# MCU.net
KiCad netlist of a schematic drawn in Altium Designer
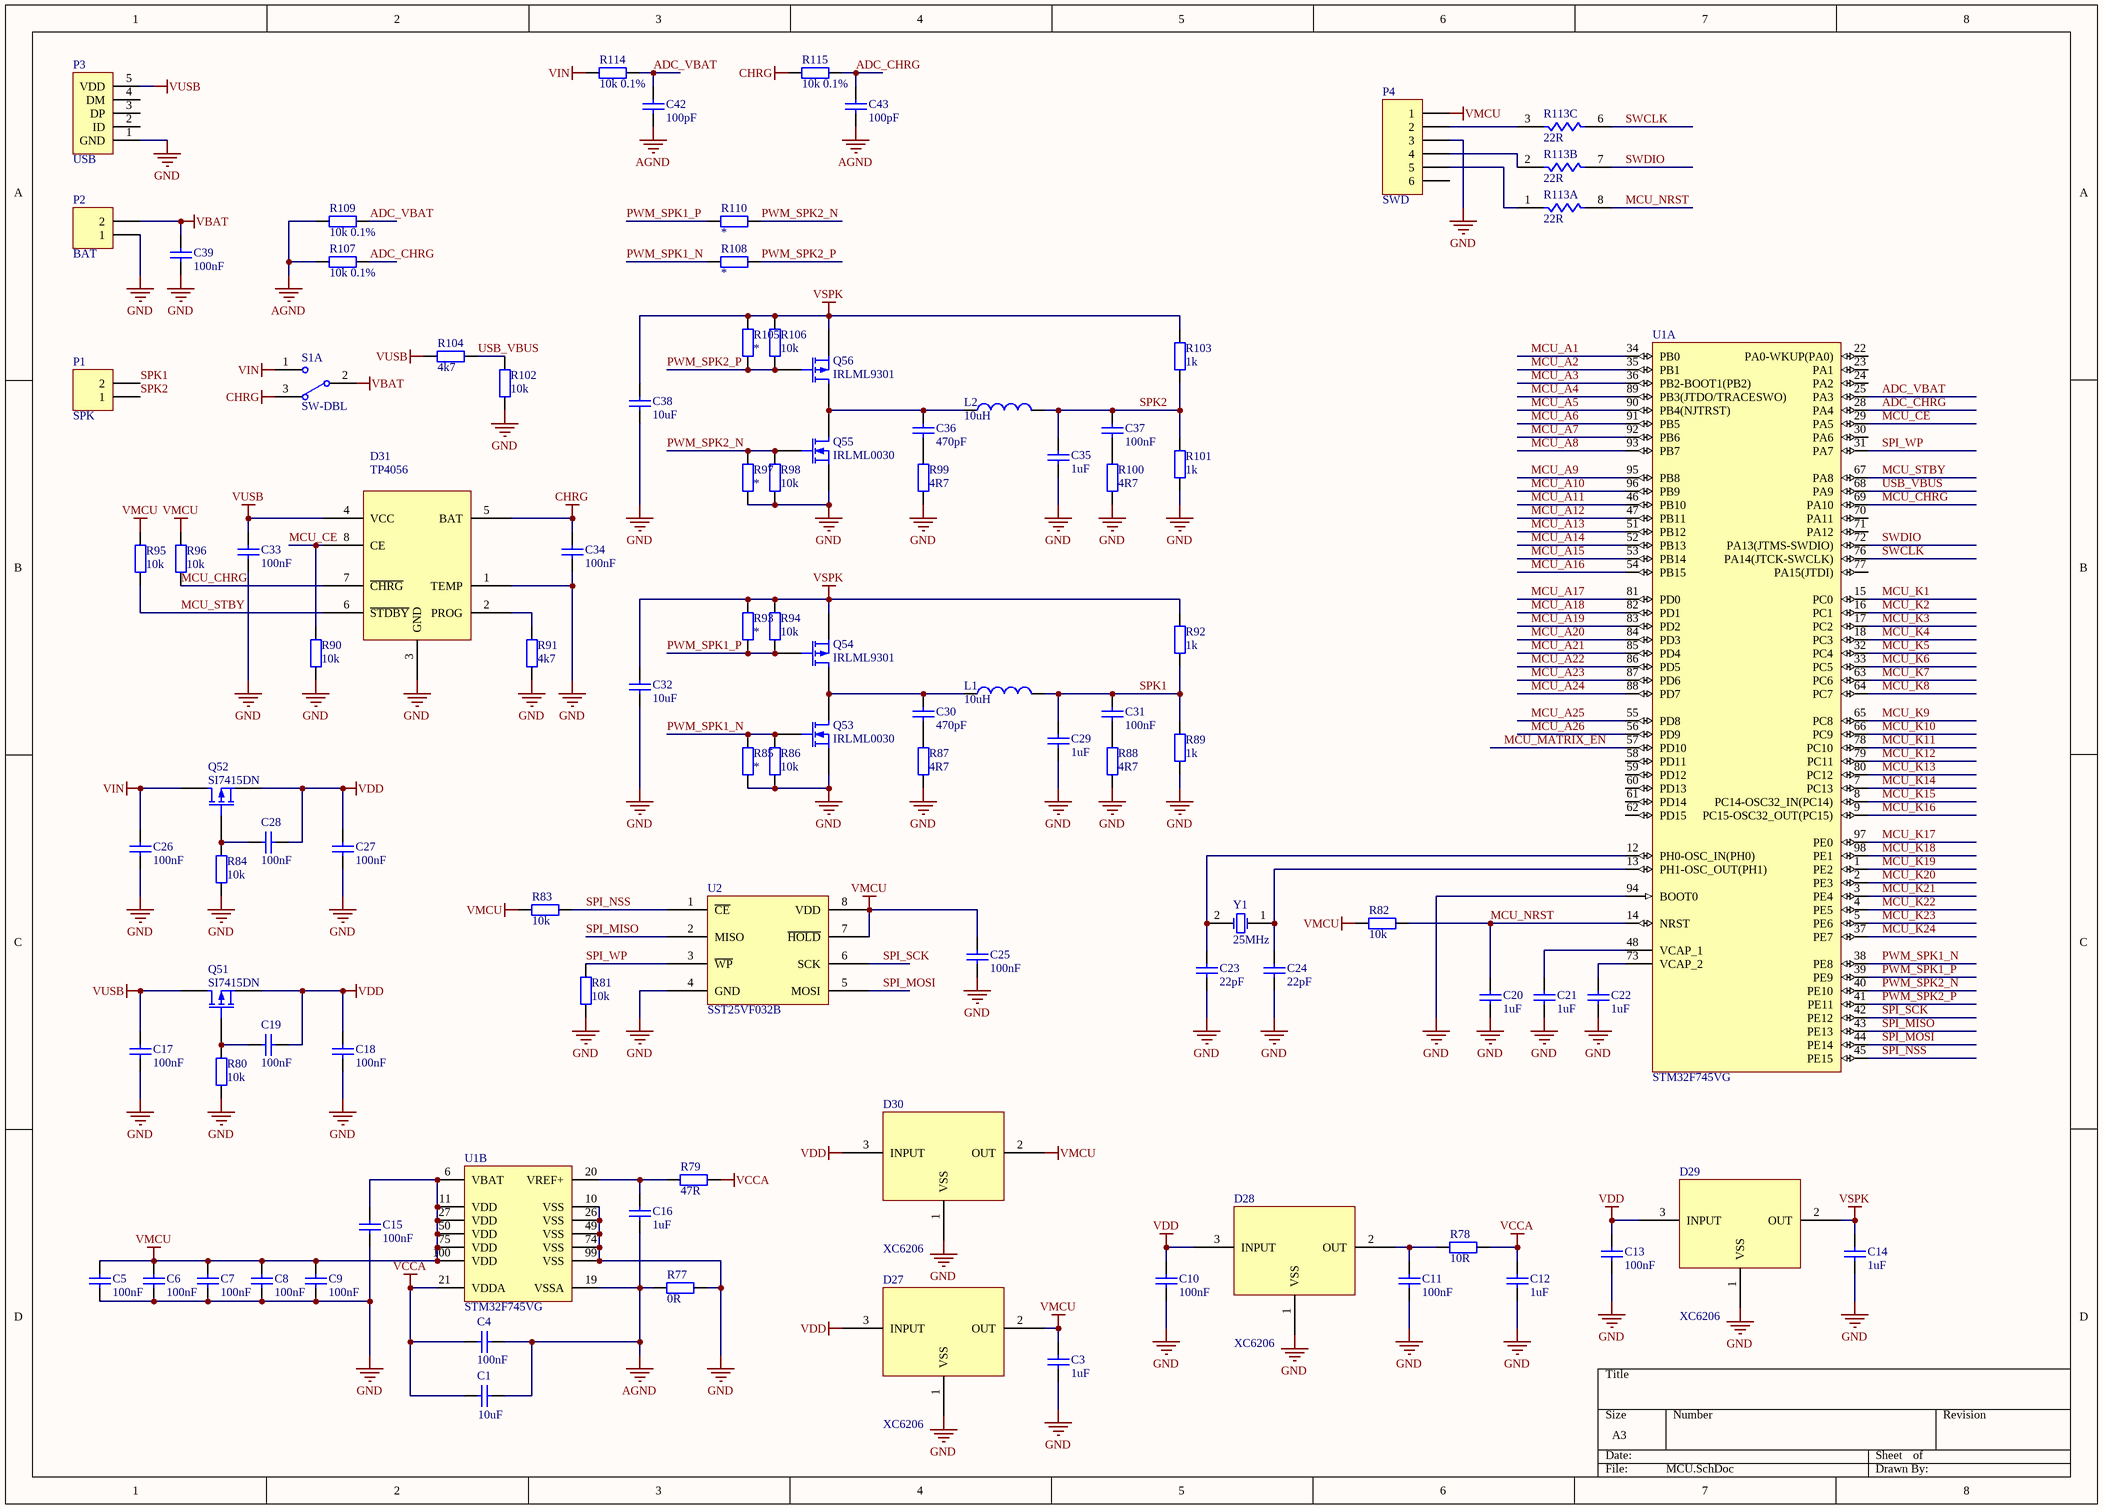
[diagram p0: MCU.SchDoc]

(export (version "E")
  (design (tool "Eeschema 10.0.6"))
  (components
    (comp (ref "C1")
      (value "10uF")
      (footprint "c1206")
      (description "Capacitor")
      (fields (field (name "Comment") "Cap") (field (name "PUBLISHER") "Altium Limited"))
      (libsource (lib "Miscellaneous Devices") (part "Cap"))
    )
    (comp (ref "C3")
      (value "1uF")
      (footprint "C0603")
      (description "Capacitor")
      (fields (field (name "Comment") "Cap") (field (name "PUBLISHER") "Altium Limited"))
      (libsource (lib "Lib_Sch") (part "Cap"))
    )
    (comp (ref "C4")
      (value "100nF")
      (footprint "C0603")
      (description "Capacitor")
      (fields (field (name "Comment") "Cap") (field (name "PUBLISHER") "Altium Limited"))
      (libsource (lib "Lib_Sch") (part "Cap"))
    )
    (comp (ref "C5")
      (value "100nF")
      (footprint "C0603")
      (description "Capacitor")
      (fields (field (name "Comment") "Cap") (field (name "PUBLISHER") "Altium Limited"))
      (libsource (lib "Lib_Sch") (part "Cap"))
    )
    (comp (ref "C6")
      (value "100nF")
      (footprint "C0603")
      (description "Capacitor")
      (fields (field (name "Comment") "Cap") (field (name "PUBLISHER") "Altium Limited"))
      (libsource (lib "Lib_Sch") (part "Cap"))
    )
    (comp (ref "C7")
      (value "100nF")
      (footprint "C0603")
      (description "Capacitor")
      (fields (field (name "Comment") "Cap") (field (name "PUBLISHER") "Altium Limited"))
      (libsource (lib "Lib_Sch") (part "Cap"))
    )
    (comp (ref "C8")
      (value "100nF")
      (footprint "C0603")
      (description "Capacitor")
      (fields (field (name "Comment") "Cap") (field (name "PUBLISHER") "Altium Limited"))
      (libsource (lib "Lib_Sch") (part "Cap"))
    )
    (comp (ref "C9")
      (value "100nF")
      (footprint "C0603")
      (description "Capacitor")
      (fields (field (name "Comment") "Cap") (field (name "PUBLISHER") "Altium Limited"))
      (libsource (lib "Lib_Sch") (part "Cap"))
    )
    (comp (ref "C10")
      (value "100nF")
      (footprint "C0603")
      (description "Capacitor")
      (fields (field (name "Comment") "Cap") (field (name "PUBLISHER") "Altium Limited"))
      (libsource (lib "Lib_Sch") (part "Cap"))
    )
    (comp (ref "C11")
      (value "100nF")
      (footprint "C0603")
      (description "Capacitor")
      (fields (field (name "Comment") "Cap") (field (name "PUBLISHER") "Altium Limited"))
      (libsource (lib "Lib_Sch") (part "Cap"))
    )
    (comp (ref "C12")
      (value "1uF")
      (footprint "C0603")
      (description "Capacitor")
      (fields (field (name "Comment") "Cap") (field (name "PUBLISHER") "Altium Limited"))
      (libsource (lib "Lib_Sch") (part "Cap"))
    )
    (comp (ref "C13")
      (value "100nF")
      (footprint "C0603")
      (description "Capacitor")
      (fields (field (name "Comment") "Cap") (field (name "PUBLISHER") "Altium Limited"))
      (libsource (lib "Lib_Sch") (part "Cap"))
    )
    (comp (ref "C14")
      (value "1uF")
      (footprint "C0603")
      (description "Capacitor")
      (fields (field (name "Comment") "Cap") (field (name "PUBLISHER") "Altium Limited"))
      (libsource (lib "Lib_Sch") (part "Cap"))
    )
    (comp (ref "C15")
      (value "100nF")
      (footprint "C0603")
      (description "Capacitor")
      (fields (field (name "Comment") "Cap") (field (name "PUBLISHER") "Altium Limited"))
      (libsource (lib "Lib_Sch") (part "Cap"))
    )
    (comp (ref "C16")
      (value "1uF")
      (footprint "C0603")
      (description "Capacitor")
      (fields (field (name "Comment") "Cap") (field (name "PUBLISHER") "Altium Limited"))
      (libsource (lib "Lib_Sch") (part "Cap"))
    )
    (comp (ref "C17")
      (value "100nF")
      (footprint "C0603")
      (description "Capacitor")
      (fields (field (name "Comment") "Cap") (field (name "PUBLISHER") "Altium Limited"))
      (libsource (lib "Lib_Sch") (part "Cap"))
    )
    (comp (ref "C18")
      (value "100nF")
      (footprint "C0603")
      (description "Capacitor")
      (fields (field (name "Comment") "Cap") (field (name "PUBLISHER") "Altium Limited"))
      (libsource (lib "Lib_Sch") (part "Cap"))
    )
    (comp (ref "C19")
      (value "100nF")
      (footprint "C0603")
      (description "Capacitor")
      (fields (field (name "Comment") "Cap") (field (name "PUBLISHER") "Altium Limited"))
      (libsource (lib "Lib_Sch") (part "Cap"))
    )
    (comp (ref "C20")
      (value "1uF")
      (footprint "C0603")
      (description "Capacitor")
      (fields (field (name "Comment") "Cap") (field (name "PUBLISHER") "Altium Limited"))
      (libsource (lib "Lib_Sch") (part "Cap"))
    )
    (comp (ref "C21")
      (value "1uF")
      (footprint "C0603")
      (description "Capacitor")
      (fields (field (name "Comment") "Cap") (field (name "PUBLISHER") "Altium Limited"))
      (libsource (lib "Lib_Sch") (part "Cap"))
    )
    (comp (ref "C22")
      (value "1uF")
      (footprint "C0603")
      (description "Capacitor")
      (fields (field (name "Comment") "Cap") (field (name "PUBLISHER") "Altium Limited"))
      (libsource (lib "Lib_Sch") (part "Cap"))
    )
    (comp (ref "C23")
      (value "22pF")
      (footprint "c0603")
      (description "Capacitor")
      (fields (field (name "PUBLISHER") "Altium Limited"))
      (libsource (lib "") (part "Cap_1"))
    )
    (comp (ref "C24")
      (value "22pF")
      (footprint "c0603")
      (description "Capacitor")
      (fields (field (name "PUBLISHER") "Altium Limited"))
      (libsource (lib "") (part "Cap_1"))
    )
    (comp (ref "C25")
      (value "100nF")
      (footprint "C0603")
      (description "Capacitor")
      (fields (field (name "Comment") "Cap") (field (name "PUBLISHER") "Altium Limited"))
      (libsource (lib "Lib_Sch") (part "Cap"))
    )
    (comp (ref "C26")
      (value "100nF")
      (footprint "C0603")
      (description "Capacitor")
      (fields (field (name "Comment") "Cap") (field (name "PUBLISHER") "Altium Limited"))
      (libsource (lib "Lib_Sch") (part "Cap"))
    )
    (comp (ref "C27")
      (value "100nF")
      (footprint "C0603")
      (description "Capacitor")
      (fields (field (name "Comment") "Cap") (field (name "PUBLISHER") "Altium Limited"))
      (libsource (lib "Lib_Sch") (part "Cap"))
    )
    (comp (ref "C28")
      (value "100nF")
      (footprint "C0603")
      (description "Capacitor")
      (fields (field (name "Comment") "Cap") (field (name "PUBLISHER") "Altium Limited"))
      (libsource (lib "Lib_Sch") (part "Cap"))
    )
    (comp (ref "C29")
      (value "1uF")
      (footprint "C0603")
      (description "Capacitor")
      (fields (field (name "Comment") "Cap") (field (name "PUBLISHER") "Altium Limited"))
      (libsource (lib "Lib_Sch") (part "Cap"))
    )
    (comp (ref "C30")
      (value "470pF")
      (footprint "C0603")
      (description "Capacitor")
      (fields (field (name "Comment") "Cap") (field (name "PUBLISHER") "Altium Limited"))
      (libsource (lib "Lib_Sch") (part "Cap"))
    )
    (comp (ref "C31")
      (value "100nF")
      (footprint "C0603")
      (description "Capacitor")
      (fields (field (name "Comment") "Cap") (field (name "PUBLISHER") "Altium Limited"))
      (libsource (lib "Lib_Sch") (part "Cap"))
    )
    (comp (ref "C32")
      (value "10uF")
      (footprint "c1206")
      (description "Capacitor")
      (fields (field (name "Comment") "Cap") (field (name "PUBLISHER") "Altium Limited"))
      (libsource (lib "Lib_Sch") (part "Cap"))
    )
    (comp (ref "C33")
      (value "100nF")
      (footprint "C0603")
      (description "Capacitor")
      (fields (field (name "Comment") "Cap") (field (name "PUBLISHER") "Altium Limited"))
      (libsource (lib "Lib_Sch") (part "Cap"))
    )
    (comp (ref "C34")
      (value "100nF")
      (footprint "C0603")
      (description "Capacitor")
      (fields (field (name "Comment") "Cap") (field (name "PUBLISHER") "Altium Limited"))
      (libsource (lib "Lib_Sch") (part "Cap"))
    )
    (comp (ref "C35")
      (value "1uF")
      (footprint "C0603")
      (description "Capacitor")
      (fields (field (name "Comment") "Cap") (field (name "PUBLISHER") "Altium Limited"))
      (libsource (lib "Lib_Sch") (part "Cap"))
    )
    (comp (ref "C36")
      (value "470pF")
      (footprint "C0603")
      (description "Capacitor")
      (fields (field (name "Comment") "Cap") (field (name "PUBLISHER") "Altium Limited"))
      (libsource (lib "Lib_Sch") (part "Cap"))
    )
    (comp (ref "C37")
      (value "100nF")
      (footprint "C0603")
      (description "Capacitor")
      (fields (field (name "Comment") "Cap") (field (name "PUBLISHER") "Altium Limited"))
      (libsource (lib "Lib_Sch") (part "Cap"))
    )
    (comp (ref "C38")
      (value "10uF")
      (footprint "c1206")
      (description "Capacitor")
      (fields (field (name "Comment") "Cap") (field (name "PUBLISHER") "Altium Limited"))
      (libsource (lib "Lib_Sch") (part "Cap"))
    )
    (comp (ref "C39")
      (value "100nF")
      (footprint "C0603")
      (description "Capacitor")
      (fields (field (name "Comment") "Cap") (field (name "PUBLISHER") "Altium Limited"))
      (libsource (lib "Lib_Sch") (part "Cap"))
    )
    (comp (ref "C42")
      (value "100pF")
      (footprint "C0603")
      (description "Capacitor")
      (fields (field (name "Comment") "Cap") (field (name "PUBLISHER") "Altium Limited"))
      (libsource (lib "Lib_Sch") (part "Cap"))
    )
    (comp (ref "C43")
      (value "100pF")
      (footprint "C0603")
      (description "Capacitor")
      (fields (field (name "Comment") "Cap") (field (name "PUBLISHER") "Altium Limited"))
      (libsource (lib "Lib_Sch") (part "Cap"))
    )
    (comp (ref "D27") (value "XC6206") (footprint "sot23") (libsource (lib "Lib_Sch") (part "XC6206")))
    (comp (ref "D28") (value "XC6206") (footprint "sot23") (libsource (lib "Lib_Sch") (part "XC6206")))
    (comp (ref "D29") (value "XC6206") (footprint "sot23") (libsource (lib "Lib_Sch") (part "XC6206")))
    (comp (ref "D30") (value "XC6206") (footprint "sot23") (libsource (lib "Lib_Sch") (part "XC6206")))
    (comp (ref "D31") (value "TP4056") (footprint "SO8_WPAD") (libsource (lib "Lib_Sch") (part "TP4056")))
    (comp (ref "L1")
      (value "10uH")
      (footprint "CD32_Inductor")
      (description "Inductor")
      (fields (field (name "PUBLISHER") "Altium Limited"))
      (libsource (lib "Miscellaneous Devices") (part "Inductor"))
    )
    (comp (ref "L2")
      (value "10uH")
      (footprint "CD32_Inductor")
      (description "Inductor")
      (fields (field (name "PUBLISHER") "Altium Limited"))
      (libsource (lib "Miscellaneous Devices") (part "Inductor"))
    )
    (comp (ref "P1")
      (value "SPK")
      (footprint "HDR1X2")
      (description "Header, 2-Pin")
      (fields (field (name "PUBLISHER") "Altium Limited"))
      (libsource (lib "Miscellaneous Connectors") (part "Header 2"))
    )
    (comp (ref "P2")
      (value "BAT")
      (footprint "HDR1X2")
      (description "Header, 2-Pin")
      (fields (field (name "PUBLISHER") "Altium Limited"))
      (libsource (lib "Miscellaneous Connectors") (part "Header 2"))
    )
    (comp (ref "P3")
      (value "USB")
      (footprint "MICRO_USB")
      (description "Header, 5-Pin")
      (fields (field (name "PUBLISHER") "Altium Limited"))
      (libsource (lib "Lib_Sch") (part "USB"))
    )
    (comp (ref "P4")
      (value "SWD")
      (footprint "HDR1X6")
      (description "Header, 6-Pin")
      (fields (field (name "PUBLISHER") "Altium Limited"))
      (libsource (lib "Miscellaneous Connectors") (part "Header 6"))
    )
    (comp (ref "Q51")
      (value "SI7415DN")
      (footprint "PowerPAK1212-8")
      (description "P-Channel MOSFET")
      (fields (field (name "PUBLISHER") "Altium Limited"))
      (libsource (lib "Lib_Sch") (part "MOSFET-P"))
    )
    (comp (ref "Q52")
      (value "SI7415DN")
      (footprint "PowerPAK1212-8")
      (description "P-Channel MOSFET")
      (fields (field (name "PUBLISHER") "Altium Limited"))
      (libsource (lib "Lib_Sch") (part "MOSFET-P"))
    )
    (comp (ref "Q53")
      (value "IRLML0030")
      (footprint "sot23")
      (description "N-Channel MOSFET")
      (fields (field (name "PUBLISHER") "Altium Limited"))
      (libsource (lib "Lib_Sch") (part "MOSFET-N"))
    )
    (comp (ref "Q54")
      (value "IRLML9301")
      (footprint "sot23")
      (description "P-Channel MOSFET")
      (fields (field (name "PUBLISHER") "Altium Limited"))
      (libsource (lib "Lib_Sch") (part "MOSFET-P"))
    )
    (comp (ref "Q55")
      (value "IRLML0030")
      (footprint "sot23")
      (description "N-Channel MOSFET")
      (fields (field (name "PUBLISHER") "Altium Limited"))
      (libsource (lib "Lib_Sch") (part "MOSFET-N"))
    )
    (comp (ref "Q56")
      (value "IRLML9301")
      (footprint "sot23")
      (description "P-Channel MOSFET")
      (fields (field (name "PUBLISHER") "Altium Limited"))
      (libsource (lib "Lib_Sch") (part "MOSFET-P"))
    )
    (comp (ref "R77")
      (value "0R")
      (footprint "r0603")
      (description "Resistor")
      (fields (field (name "PUBLISHER") "Altium Limited"))
      (libsource (lib "Lib_Sch") (part "Resistor"))
    )
    (comp (ref "R78")
      (value "10R")
      (footprint "r0603")
      (description "Resistor")
      (fields (field (name "PUBLISHER") "Altium Limited"))
      (libsource (lib "Lib_Sch") (part "Resistor"))
    )
    (comp (ref "R79")
      (value "47R")
      (footprint "r0603")
      (description "Resistor")
      (fields (field (name "PUBLISHER") "Altium Limited"))
      (libsource (lib "Lib_Sch") (part "Resistor"))
    )
    (comp (ref "R80")
      (value "10k")
      (footprint "r0603")
      (description "Resistor")
      (fields (field (name "PUBLISHER") "Altium Limited"))
      (libsource (lib "") (part "Resistor_2"))
    )
    (comp (ref "R81")
      (value "10k")
      (footprint "r0603")
      (description "Resistor")
      (fields (field (name "PUBLISHER") "Altium Limited"))
      (libsource (lib "") (part "Resistor_2"))
    )
    (comp (ref "R82")
      (value "10k")
      (footprint "r0603")
      (description "Resistor")
      (fields (field (name "PUBLISHER") "Altium Limited"))
      (libsource (lib "") (part "Resistor_2"))
    )
    (comp (ref "R83")
      (value "10k")
      (footprint "r0603")
      (description "Resistor")
      (fields (field (name "PUBLISHER") "Altium Limited"))
      (libsource (lib "Lib_Sch") (part "Resistor"))
    )
    (comp (ref "R84")
      (value "10k")
      (footprint "r0603")
      (description "Resistor")
      (fields (field (name "PUBLISHER") "Altium Limited"))
      (libsource (lib "") (part "Resistor_2"))
    )
    (comp (ref "R85")
      (value "Resistor")
      (footprint "n0603")
      (fields (field (name "ALTIUM_VALUE") "*") (field (name "PUBLISHER") "Altium Limited"))
      (libsource (lib "") (part "Resistor_2"))
    )
    (comp (ref "R86")
      (value "10k")
      (footprint "r0603")
      (description "Resistor")
      (fields (field (name "PUBLISHER") "Altium Limited"))
      (libsource (lib "") (part "Resistor_2"))
    )
    (comp (ref "R87")
      (value "4R7")
      (footprint "r0603")
      (description "Resistor")
      (fields (field (name "PUBLISHER") "Altium Limited"))
      (libsource (lib "") (part "Resistor_2"))
    )
    (comp (ref "R88")
      (value "4R7")
      (footprint "r0603")
      (description "Resistor")
      (fields (field (name "PUBLISHER") "Altium Limited"))
      (libsource (lib "") (part "Resistor_2"))
    )
    (comp (ref "R89")
      (value "1k")
      (footprint "r0603")
      (description "Resistor")
      (fields (field (name "PUBLISHER") "Altium Limited"))
      (libsource (lib "") (part "Resistor_2"))
    )
    (comp (ref "R90")
      (value "10k")
      (footprint "r0603")
      (description "Resistor")
      (fields (field (name "PUBLISHER") "Altium Limited"))
      (libsource (lib "") (part "Resistor_2"))
    )
    (comp (ref "R91")
      (value "4k7")
      (footprint "r0603")
      (description "Resistor")
      (fields (field (name "PUBLISHER") "Altium Limited"))
      (libsource (lib "") (part "Resistor_2"))
    )
    (comp (ref "R92")
      (value "1k")
      (footprint "r0603")
      (description "Resistor")
      (fields (field (name "PUBLISHER") "Altium Limited"))
      (libsource (lib "") (part "Resistor_2"))
    )
    (comp (ref "R93")
      (value "Resistor")
      (footprint "n0603")
      (fields (field (name "ALTIUM_VALUE") "*") (field (name "PUBLISHER") "Altium Limited"))
      (libsource (lib "") (part "Resistor_2"))
    )
    (comp (ref "R94")
      (value "10k")
      (footprint "r0603")
      (description "Resistor")
      (fields (field (name "PUBLISHER") "Altium Limited"))
      (libsource (lib "") (part "Resistor_2"))
    )
    (comp (ref "R95")
      (value "10k")
      (footprint "r0603")
      (description "Resistor")
      (fields (field (name "PUBLISHER") "Altium Limited"))
      (libsource (lib "") (part "Resistor_2"))
    )
    (comp (ref "R96")
      (value "10k")
      (footprint "r0603")
      (description "Resistor")
      (fields (field (name "PUBLISHER") "Altium Limited"))
      (libsource (lib "") (part "Resistor_2"))
    )
    (comp (ref "R97")
      (value "Resistor")
      (footprint "n0603")
      (fields (field (name "ALTIUM_VALUE") "*") (field (name "PUBLISHER") "Altium Limited"))
      (libsource (lib "") (part "Resistor_2"))
    )
    (comp (ref "R98")
      (value "10k")
      (footprint "r0603")
      (description "Resistor")
      (fields (field (name "PUBLISHER") "Altium Limited"))
      (libsource (lib "") (part "Resistor_2"))
    )
    (comp (ref "R99")
      (value "4R7")
      (footprint "r0603")
      (description "Resistor")
      (fields (field (name "PUBLISHER") "Altium Limited"))
      (libsource (lib "") (part "Resistor_2"))
    )
    (comp (ref "R100")
      (value "4R7")
      (footprint "r0603")
      (description "Resistor")
      (fields (field (name "PUBLISHER") "Altium Limited"))
      (libsource (lib "") (part "Resistor_2"))
    )
    (comp (ref "R101")
      (value "1k")
      (footprint "r0603")
      (description "Resistor")
      (fields (field (name "PUBLISHER") "Altium Limited"))
      (libsource (lib "") (part "Resistor_2"))
    )
    (comp (ref "R102")
      (value "10k")
      (footprint "r0603")
      (description "Resistor")
      (fields (field (name "PUBLISHER") "Altium Limited"))
      (libsource (lib "") (part "Resistor_3"))
    )
    (comp (ref "R103")
      (value "1k")
      (footprint "r0603")
      (description "Resistor")
      (fields (field (name "PUBLISHER") "Altium Limited"))
      (libsource (lib "") (part "Resistor_2"))
    )
    (comp (ref "R104")
      (value "4k7")
      (footprint "r0603")
      (description "Resistor")
      (fields (field (name "PUBLISHER") "Altium Limited"))
      (libsource (lib "") (part "Resistor_1"))
    )
    (comp (ref "R105")
      (value "Resistor")
      (footprint "n0603")
      (fields (field (name "ALTIUM_VALUE") "*") (field (name "PUBLISHER") "Altium Limited"))
      (libsource (lib "") (part "Resistor_2"))
    )
    (comp (ref "R106")
      (value "10k")
      (footprint "r0603")
      (description "Resistor")
      (fields (field (name "PUBLISHER") "Altium Limited"))
      (libsource (lib "") (part "Resistor_2"))
    )
    (comp (ref "R107")
      (value "10k 0.1%")
      (footprint "r0603")
      (description "Resistor")
      (fields (field (name "PUBLISHER") "Altium Limited"))
      (libsource (lib "") (part "Resistor_1"))
    )
    (comp (ref "R108")
      (value "Resistor")
      (footprint "n0603")
      (fields (field (name "ALTIUM_VALUE") "*") (field (name "PUBLISHER") "Altium Limited"))
      (libsource (lib "") (part "Resistor_1"))
    )
    (comp (ref "R109")
      (value "10k 0.1%")
      (footprint "r0603")
      (description "Resistor")
      (fields (field (name "PUBLISHER") "Altium Limited"))
      (libsource (lib "") (part "Resistor_1"))
    )
    (comp (ref "R110")
      (value "Resistor")
      (footprint "n0603")
      (fields (field (name "ALTIUM_VALUE") "*") (field (name "PUBLISHER") "Altium Limited"))
      (libsource (lib "") (part "Resistor_1"))
    )
    (comp (ref "R113")
      (value "22R")
      (footprint "R1206_PACK")
      (description "Isolated Resistor Network - Parts")
      (fields (field (name "Comment") "Res Pack 1206") (field (name "PUBLISHER") "Altium Limited"))
      (libsource (lib "Lib_Sch") (part "Res Pack 1206"))
    )
    (comp (ref "R114")
      (value "10k 0.1%")
      (footprint "r0603")
      (description "Resistor")
      (fields (field (name "PUBLISHER") "Altium Limited"))
      (libsource (lib "") (part "Resistor_1"))
    )
    (comp (ref "R115")
      (value "10k 0.1%")
      (footprint "r0603")
      (description "Resistor")
      (fields (field (name "PUBLISHER") "Altium Limited"))
      (libsource (lib "") (part "Resistor_1"))
    )
    (comp (ref "S1")
      (value "SW-DBL")
      (footprint "SK-22D07VG5")
      (description "SPDT Subminiature Toggle Switch, Right Angle Mounting, Vertical Actuation")
      (fields (field (name "PUBLISHER") "Altium Limited"))
      (libsource (lib "Lib_Sch") (part "SW-DBL"))
    )
    (comp (ref "U1")
      (value "STM32F745VG")
      (footprint "lqfp100_m")
      (fields (field (name "MANUFACTURER") "STMicroelectronics") (field (name "PARTNUMBER") "STM32F407VGT6"))
      (libsource (lib "") (part "STM32F746VG_1"))
    )
    (comp (ref "U2")
      (value "SST25VF032B")
      (footprint "SO8_25EE")
      (libsource (lib "Lib_Sch") (part "EEPROM_SPI"))
    )
    (comp (ref "Y1")
      (value "25MHz")
      (footprint "KX-7")
      (description "Crystal Oscillator")
      (fields (field (name "PUBLISHER") "Altium Limited"))
      (libsource (lib "Lib_Sch") (part "XTAL_4pin"))
    )
  )
  (nets
    (net (code "1") (name "/ADC_CHRG") (class "Default")
      (node (ref "C43") (pin "2") (pinfunction "2_2") (pintype "passive"))
      (node (ref "R107") (pin "1") (pinfunction "1_1") (pintype "passive"))
      (node (ref "R115") (pin "1") (pinfunction "1_1") (pintype "passive"))
      (node (ref "U1") (pin "28") (pinfunction "PA4_28") (pintype "bidirectional"))
    )
    (net (code "2") (name "/ADC_VBAT") (class "Default")
      (node (ref "C42") (pin "2") (pinfunction "2_2") (pintype "passive"))
      (node (ref "R109") (pin "1") (pinfunction "1_1") (pintype "passive"))
      (node (ref "R114") (pin "1") (pinfunction "1_1") (pintype "passive"))
      (node (ref "U1") (pin "25") (pinfunction "PA3_25") (pintype "bidirectional"))
    )
    (net (code "3") (name "/MCU_A1") (class "Default")
      (node (ref "U1") (pin "34") (pinfunction "PB0_34") (pintype "bidirectional"))
    )
    (net (code "4") (name "/MCU_A2") (class "Default")
      (node (ref "U1") (pin "35") (pinfunction "PB1_35") (pintype "bidirectional"))
    )
    (net (code "5") (name "/MCU_A3") (class "Default")
      (node (ref "U1") (pin "36") (pinfunction "PB2-BOOT1(PB2)_36") (pintype "bidirectional"))
    )
    (net (code "6") (name "/MCU_A4") (class "Default")
      (node (ref "U1") (pin "89") (pinfunction "PB3(JTDO/TRACESWO)_89") (pintype "bidirectional"))
    )
    (net (code "7") (name "/MCU_A5") (class "Default")
      (node (ref "U1") (pin "90") (pinfunction "PB4(NJTRST)_90") (pintype "bidirectional"))
    )
    (net (code "8") (name "/MCU_A6") (class "Default")
      (node (ref "U1") (pin "91") (pinfunction "PB5_91") (pintype "bidirectional"))
    )
    (net (code "9") (name "/MCU_A7") (class "Default")
      (node (ref "U1") (pin "92") (pinfunction "PB6_92") (pintype "bidirectional"))
    )
    (net (code "10") (name "/MCU_A8") (class "Default")
      (node (ref "U1") (pin "93") (pinfunction "PB7_93") (pintype "bidirectional"))
    )
    (net (code "11") (name "/MCU_A9") (class "Default")
      (node (ref "U1") (pin "95") (pinfunction "PB8_95") (pintype "bidirectional"))
    )
    (net (code "12") (name "/MCU_A10") (class "Default")
      (node (ref "U1") (pin "96") (pinfunction "PB9_96") (pintype "bidirectional"))
    )
    (net (code "13") (name "/MCU_A11") (class "Default")
      (node (ref "U1") (pin "46") (pinfunction "PB10_46") (pintype "bidirectional"))
    )
    (net (code "14") (name "/MCU_A12") (class "Default")
      (node (ref "U1") (pin "47") (pinfunction "PB11_47") (pintype "bidirectional"))
    )
    (net (code "15") (name "/MCU_A13") (class "Default")
      (node (ref "U1") (pin "51") (pinfunction "PB12_51") (pintype "bidirectional"))
    )
    (net (code "16") (name "/MCU_A14") (class "Default")
      (node (ref "U1") (pin "52") (pinfunction "PB13_52") (pintype "bidirectional"))
    )
    (net (code "17") (name "/MCU_A15") (class "Default")
      (node (ref "U1") (pin "53") (pinfunction "PB14_53") (pintype "bidirectional"))
    )
    (net (code "18") (name "/MCU_A16") (class "Default")
      (node (ref "U1") (pin "54") (pinfunction "PB15_54") (pintype "bidirectional"))
    )
    (net (code "19") (name "/MCU_A17") (class "Default")
      (node (ref "U1") (pin "81") (pinfunction "PD0_81") (pintype "bidirectional"))
    )
    (net (code "20") (name "/MCU_A18") (class "Default")
      (node (ref "U1") (pin "82") (pinfunction "PD1_82") (pintype "bidirectional"))
    )
    (net (code "21") (name "/MCU_A19") (class "Default")
      (node (ref "U1") (pin "83") (pinfunction "PD2_83") (pintype "bidirectional"))
    )
    (net (code "22") (name "/MCU_A20") (class "Default")
      (node (ref "U1") (pin "84") (pinfunction "PD3_84") (pintype "bidirectional"))
    )
    (net (code "23") (name "/MCU_A21") (class "Default")
      (node (ref "U1") (pin "85") (pinfunction "PD4_85") (pintype "bidirectional"))
    )
    (net (code "24") (name "/MCU_A22") (class "Default")
      (node (ref "U1") (pin "86") (pinfunction "PD5_86") (pintype "bidirectional"))
    )
    (net (code "25") (name "/MCU_A23") (class "Default")
      (node (ref "U1") (pin "87") (pinfunction "PD6_87") (pintype "bidirectional"))
    )
    (net (code "26") (name "/MCU_A24") (class "Default")
      (node (ref "U1") (pin "88") (pinfunction "PD7_88") (pintype "bidirectional"))
    )
    (net (code "27") (name "/MCU_A25") (class "Default")
      (node (ref "U1") (pin "55") (pinfunction "PD8_55") (pintype "bidirectional"))
    )
    (net (code "28") (name "/MCU_A26") (class "Default")
      (node (ref "U1") (pin "56") (pinfunction "PD9_56") (pintype "bidirectional"))
    )
    (net (code "29") (name "/MCU_CE") (class "Default")
      (node (ref "D31") (pin "8") (pinfunction "CE_8") (pintype "passive"))
      (node (ref "R90") (pin "2") (pinfunction "2_2") (pintype "passive"))
      (node (ref "U1") (pin "29") (pinfunction "PA5_29") (pintype "bidirectional"))
    )
    (net (code "30") (name "/MCU_CHRG") (class "Default")
      (node (ref "D31") (pin "7") (pinfunction "~{CHRG}_7") (pintype "passive"))
      (node (ref "R96") (pin "1") (pinfunction "1_1") (pintype "passive"))
      (node (ref "U1") (pin "69") (pinfunction "PA10_69") (pintype "bidirectional"))
    )
    (net (code "31") (name "/MCU_K1") (class "Default")
      (node (ref "U1") (pin "15") (pinfunction "PC0_15") (pintype "bidirectional"))
    )
    (net (code "32") (name "/MCU_K2") (class "Default")
      (node (ref "U1") (pin "16") (pinfunction "PC1_16") (pintype "bidirectional"))
    )
    (net (code "33") (name "/MCU_K3") (class "Default")
      (node (ref "U1") (pin "17") (pinfunction "PC2_17") (pintype "bidirectional"))
    )
    (net (code "34") (name "/MCU_K4") (class "Default")
      (node (ref "U1") (pin "18") (pinfunction "PC3_18") (pintype "bidirectional"))
    )
    (net (code "35") (name "/MCU_K5") (class "Default")
      (node (ref "U1") (pin "32") (pinfunction "PC4_32") (pintype "bidirectional"))
    )
    (net (code "36") (name "/MCU_K6") (class "Default")
      (node (ref "U1") (pin "33") (pinfunction "PC5_33") (pintype "bidirectional"))
    )
    (net (code "37") (name "/MCU_K7") (class "Default")
      (node (ref "U1") (pin "63") (pinfunction "PC6_63") (pintype "bidirectional"))
    )
    (net (code "38") (name "/MCU_K8") (class "Default")
      (node (ref "U1") (pin "64") (pinfunction "PC7_64") (pintype "bidirectional"))
    )
    (net (code "39") (name "/MCU_K9") (class "Default")
      (node (ref "U1") (pin "65") (pinfunction "PC8_65") (pintype "bidirectional"))
    )
    (net (code "40") (name "/MCU_K10") (class "Default")
      (node (ref "U1") (pin "66") (pinfunction "PC9_66") (pintype "bidirectional"))
    )
    (net (code "41") (name "/MCU_K11") (class "Default")
      (node (ref "U1") (pin "78") (pinfunction "PC10_78") (pintype "bidirectional"))
    )
    (net (code "42") (name "/MCU_K12") (class "Default")
      (node (ref "U1") (pin "79") (pinfunction "PC11_79") (pintype "bidirectional"))
    )
    (net (code "43") (name "/MCU_K13") (class "Default")
      (node (ref "U1") (pin "80") (pinfunction "PC12_80") (pintype "bidirectional"))
    )
    (net (code "44") (name "/MCU_K14") (class "Default")
      (node (ref "U1") (pin "7") (pinfunction "PC13_7") (pintype "bidirectional"))
    )
    (net (code "45") (name "/MCU_K15") (class "Default")
      (node (ref "U1") (pin "8") (pinfunction "PC14-OSC32_IN(PC14)_8") (pintype "bidirectional"))
    )
    (net (code "46") (name "/MCU_K16") (class "Default")
      (node (ref "U1") (pin "9") (pinfunction "PC15-OSC32_OUT(PC15)_9") (pintype "bidirectional"))
    )
    (net (code "47") (name "/MCU_K17") (class "Default")
      (node (ref "U1") (pin "97") (pinfunction "PE0_97") (pintype "bidirectional"))
    )
    (net (code "48") (name "/MCU_K18") (class "Default")
      (node (ref "U1") (pin "98") (pinfunction "PE1_98") (pintype "bidirectional"))
    )
    (net (code "49") (name "/MCU_K19") (class "Default")
      (node (ref "U1") (pin "1") (pinfunction "PE2_1") (pintype "bidirectional"))
    )
    (net (code "50") (name "/MCU_K20") (class "Default")
      (node (ref "U1") (pin "2") (pinfunction "PE3_2") (pintype "bidirectional"))
    )
    (net (code "51") (name "/MCU_K21") (class "Default")
      (node (ref "U1") (pin "3") (pinfunction "PE4_3") (pintype "bidirectional"))
    )
    (net (code "52") (name "/MCU_K22") (class "Default")
      (node (ref "U1") (pin "4") (pinfunction "PE5_4") (pintype "bidirectional"))
    )
    (net (code "53") (name "/MCU_K23") (class "Default")
      (node (ref "U1") (pin "5") (pinfunction "PE6_5") (pintype "bidirectional"))
    )
    (net (code "54") (name "/MCU_K24") (class "Default")
      (node (ref "U1") (pin "37") (pinfunction "PE7_37") (pintype "bidirectional"))
    )
    (net (code "55") (name "/MCU_MATRIX_EN") (class "Default")
      (node (ref "U1") (pin "57") (pinfunction "PD10_57") (pintype "bidirectional"))
    )
    (net (code "56") (name "/MCU_NRST") (class "Default")
      (node (ref "C20") (pin "2") (pinfunction "2_2") (pintype "passive"))
      (node (ref "R113") (pin "8") (pinfunction "8_8") (pintype "passive"))
      (node (ref "R82") (pin "2") (pinfunction "2_2") (pintype "passive"))
      (node (ref "U1") (pin "14") (pinfunction "NRST_14") (pintype "bidirectional"))
    )
    (net (code "57") (name "/MCU_STBY") (class "Default")
      (node (ref "D31") (pin "6") (pinfunction "~{STDBY}_6") (pintype "passive"))
      (node (ref "R95") (pin "1") (pinfunction "1_1") (pintype "passive"))
      (node (ref "U1") (pin "67") (pinfunction "PA8_67") (pintype "bidirectional"))
    )
    (net (code "58") (name "/PWM_SPK1_N") (class "Default")
      (node (ref "Q53") (pin "1") (pinfunction "G_1") (pintype "passive"))
      (node (ref "R108") (pin "2") (pinfunction "2_2") (pintype "passive"))
      (node (ref "R85") (pin "2") (pinfunction "2_2") (pintype "passive"))
      (node (ref "R86") (pin "2") (pinfunction "2_2") (pintype "passive"))
      (node (ref "U1") (pin "38") (pinfunction "PE8_38") (pintype "bidirectional"))
    )
    (net (code "59") (name "/PWM_SPK1_P") (class "Default")
      (node (ref "Q54") (pin "1") (pinfunction "G_1") (pintype "passive"))
      (node (ref "R110") (pin "2") (pinfunction "2_2") (pintype "passive"))
      (node (ref "R93") (pin "1") (pinfunction "1_1") (pintype "passive"))
      (node (ref "R94") (pin "1") (pinfunction "1_1") (pintype "passive"))
      (node (ref "U1") (pin "39") (pinfunction "PE9_39") (pintype "bidirectional"))
    )
    (net (code "60") (name "/PWM_SPK2_N") (class "Default")
      (node (ref "Q55") (pin "1") (pinfunction "G_1") (pintype "passive"))
      (node (ref "R110") (pin "1") (pinfunction "1_1") (pintype "passive"))
      (node (ref "R97") (pin "2") (pinfunction "2_2") (pintype "passive"))
      (node (ref "R98") (pin "2") (pinfunction "2_2") (pintype "passive"))
      (node (ref "U1") (pin "40") (pinfunction "PE10_40") (pintype "bidirectional"))
    )
    (net (code "61") (name "/PWM_SPK2_P") (class "Default")
      (node (ref "Q56") (pin "1") (pinfunction "G_1") (pintype "passive"))
      (node (ref "R105") (pin "1") (pinfunction "1_1") (pintype "passive"))
      (node (ref "R106") (pin "1") (pinfunction "1_1") (pintype "passive"))
      (node (ref "R108") (pin "1") (pinfunction "1_1") (pintype "passive"))
      (node (ref "U1") (pin "41") (pinfunction "PE11_41") (pintype "bidirectional"))
    )
    (net (code "62") (name "/SPI_MISO") (class "Default")
      (node (ref "U1") (pin "43") (pinfunction "PE13_43") (pintype "bidirectional"))
      (node (ref "U2") (pin "2") (pinfunction "MISO_2") (pintype "passive"))
    )
    (net (code "63") (name "/SPI_MOSI") (class "Default")
      (node (ref "U1") (pin "44") (pinfunction "PE14_44") (pintype "bidirectional"))
      (node (ref "U2") (pin "5") (pinfunction "MOSI_5") (pintype "passive"))
    )
    (net (code "64") (name "/SPI_NSS") (class "Default")
      (node (ref "R83") (pin "2") (pinfunction "2_2") (pintype "passive"))
      (node (ref "U1") (pin "45") (pinfunction "PE15_45") (pintype "bidirectional"))
      (node (ref "U2") (pin "1") (pinfunction "~{CE}_1") (pintype "passive"))
    )
    (net (code "65") (name "/SPI_SCK") (class "Default")
      (node (ref "U1") (pin "42") (pinfunction "PE12_42") (pintype "bidirectional"))
      (node (ref "U2") (pin "6") (pinfunction "SCK_6") (pintype "passive"))
    )
    (net (code "66") (name "/SPI_WP") (class "Default")
      (node (ref "R81") (pin "2") (pinfunction "2_2") (pintype "passive"))
      (node (ref "U1") (pin "31") (pinfunction "PA7_31") (pintype "bidirectional"))
      (node (ref "U2") (pin "3") (pinfunction "~{WP}_3") (pintype "passive"))
    )
    (net (code "67") (name "/SPK1") (class "Default")
      (node (ref "C29") (pin "2") (pinfunction "2_2") (pintype "passive"))
      (node (ref "C31") (pin "2") (pinfunction "2_2") (pintype "passive"))
      (node (ref "L1") (pin "2") (pinfunction "2_2") (pintype "passive"))
      (node (ref "P1") (pin "2") (pinfunction "2_2") (pintype "passive"))
      (node (ref "R89") (pin "2") (pinfunction "2_2") (pintype "passive"))
      (node (ref "R92") (pin "1") (pinfunction "1_1") (pintype "passive"))
    )
    (net (code "68") (name "/SPK2") (class "Default")
      (node (ref "C35") (pin "2") (pinfunction "2_2") (pintype "passive"))
      (node (ref "C37") (pin "2") (pinfunction "2_2") (pintype "passive"))
      (node (ref "L2") (pin "2") (pinfunction "2_2") (pintype "passive"))
      (node (ref "P1") (pin "1") (pinfunction "1_1") (pintype "passive"))
      (node (ref "R101") (pin "2") (pinfunction "2_2") (pintype "passive"))
      (node (ref "R103") (pin "1") (pinfunction "1_1") (pintype "passive"))
    )
    (net (code "69") (name "/SWCLK") (class "Default")
      (node (ref "R113") (pin "6") (pinfunction "6_6") (pintype "passive"))
      (node (ref "U1") (pin "76") (pinfunction "PA14(JTCK-SWCLK)_76") (pintype "bidirectional"))
    )
    (net (code "70") (name "/SWDIO") (class "Default")
      (node (ref "R113") (pin "7") (pinfunction "7_7") (pintype "passive"))
      (node (ref "U1") (pin "72") (pinfunction "PA13(JTMS-SWDIO)_72") (pintype "bidirectional"))
    )
    (net (code "71") (name "/USB_VBUS") (class "Default")
      (node (ref "R102") (pin "1") (pinfunction "1_1") (pintype "passive"))
      (node (ref "R104") (pin "1") (pinfunction "1_1") (pintype "passive"))
      (node (ref "U1") (pin "68") (pinfunction "PA9_68") (pintype "bidirectional"))
    )
    (net (code "72") (name "AGND") (class "Default")
      (node (ref "C1") (pin "2") (pinfunction "2_2") (pintype "passive"))
      (node (ref "C16") (pin "1") (pinfunction "1_1") (pintype "passive"))
      (node (ref "C4") (pin "2") (pinfunction "2_2") (pintype "passive"))
      (node (ref "C42") (pin "1") (pinfunction "1_1") (pintype "passive"))
      (node (ref "C43") (pin "1") (pinfunction "1_1") (pintype "passive"))
      (node (ref "R107") (pin "2") (pinfunction "2_2") (pintype "passive"))
      (node (ref "R109") (pin "2") (pinfunction "2_2") (pintype "passive"))
      (node (ref "R77") (pin "1") (pinfunction "1_1") (pintype "passive"))
      (node (ref "U1") (pin "19") (pinfunction "VSSA_19") (pintype "power_in"))
    )
    (net (code "73") (name "CHRG") (class "Default")
      (node (ref "C34") (pin "2") (pinfunction "2_2") (pintype "passive"))
      (node (ref "D31") (pin "5") (pinfunction "BAT_5") (pintype "passive"))
      (node (ref "R115") (pin "2") (pinfunction "2_2") (pintype "passive"))
      (node (ref "S1") (pin "3") (pinfunction "3_3") (pintype "passive"))
    )
    (net (code "74") (name "GND") (class "Default")
      (node (ref "C10") (pin "1") (pinfunction "1_1") (pintype "passive"))
      (node (ref "C11") (pin "1") (pinfunction "1_1") (pintype "passive"))
      (node (ref "C12") (pin "1") (pinfunction "1_1") (pintype "passive"))
      (node (ref "C13") (pin "1") (pinfunction "1_1") (pintype "passive"))
      (node (ref "C14") (pin "1") (pinfunction "1_1") (pintype "passive"))
      (node (ref "C15") (pin "1") (pinfunction "1_1") (pintype "passive"))
      (node (ref "C17") (pin "1") (pinfunction "1_1") (pintype "passive"))
      (node (ref "C18") (pin "1") (pinfunction "1_1") (pintype "passive"))
      (node (ref "C20") (pin "1") (pinfunction "1_1") (pintype "passive"))
      (node (ref "C21") (pin "1") (pinfunction "1_1") (pintype "passive"))
      (node (ref "C22") (pin "1") (pinfunction "1_1") (pintype "passive"))
      (node (ref "C23") (pin "2") (pinfunction "2_2") (pintype "passive"))
      (node (ref "C24") (pin "2") (pinfunction "2_2") (pintype "passive"))
      (node (ref "C25") (pin "1") (pinfunction "1_1") (pintype "passive"))
      (node (ref "C26") (pin "1") (pinfunction "1_1") (pintype "passive"))
      (node (ref "C27") (pin "1") (pinfunction "1_1") (pintype "passive"))
      (node (ref "C29") (pin "1") (pinfunction "1_1") (pintype "passive"))
      (node (ref "C3") (pin "1") (pinfunction "1_1") (pintype "passive"))
      (node (ref "C32") (pin "1") (pinfunction "1_1") (pintype "passive"))
      (node (ref "C33") (pin "1") (pinfunction "1_1") (pintype "passive"))
      (node (ref "C34") (pin "1") (pinfunction "1_1") (pintype "passive"))
      (node (ref "C35") (pin "1") (pinfunction "1_1") (pintype "passive"))
      (node (ref "C38") (pin "1") (pinfunction "1_1") (pintype "passive"))
      (node (ref "C39") (pin "1") (pinfunction "1_1") (pintype "passive"))
      (node (ref "C5") (pin "1") (pinfunction "1_1") (pintype "passive"))
      (node (ref "C6") (pin "1") (pinfunction "1_1") (pintype "passive"))
      (node (ref "C7") (pin "1") (pinfunction "1_1") (pintype "passive"))
      (node (ref "C8") (pin "1") (pinfunction "1_1") (pintype "passive"))
      (node (ref "C9") (pin "1") (pinfunction "1_1") (pintype "passive"))
      (node (ref "D27") (pin "1") (pinfunction "VSS_1") (pintype "passive"))
      (node (ref "D28") (pin "1") (pinfunction "VSS_1") (pintype "passive"))
      (node (ref "D29") (pin "1") (pinfunction "VSS_1") (pintype "passive"))
      (node (ref "D30") (pin "1") (pinfunction "VSS_1") (pintype "passive"))
      (node (ref "D31") (pin "1") (pinfunction "TEMP_1") (pintype "passive"))
      (node (ref "D31") (pin "3") (pinfunction "GND_3") (pintype "passive"))
      (node (ref "P2") (pin "1") (pinfunction "1_1") (pintype "passive"))
      (node (ref "P3") (pin "1") (pinfunction "GND_1") (pintype "passive"))
      (node (ref "P4") (pin "3") (pinfunction "3_3") (pintype "passive"))
      (node (ref "Q53") (pin "2") (pinfunction "S_2") (pintype "passive"))
      (node (ref "Q55") (pin "2") (pinfunction "S_2") (pintype "passive"))
      (node (ref "R100") (pin "1") (pinfunction "1_1") (pintype "passive"))
      (node (ref "R101") (pin "1") (pinfunction "1_1") (pintype "passive"))
      (node (ref "R102") (pin "2") (pinfunction "2_2") (pintype "passive"))
      (node (ref "R77") (pin "2") (pinfunction "2_2") (pintype "passive"))
      (node (ref "R80") (pin "1") (pinfunction "1_1") (pintype "passive"))
      (node (ref "R81") (pin "1") (pinfunction "1_1") (pintype "passive"))
      (node (ref "R84") (pin "1") (pinfunction "1_1") (pintype "passive"))
      (node (ref "R85") (pin "1") (pinfunction "1_1") (pintype "passive"))
      (node (ref "R86") (pin "1") (pinfunction "1_1") (pintype "passive"))
      (node (ref "R87") (pin "1") (pinfunction "1_1") (pintype "passive"))
      (node (ref "R88") (pin "1") (pinfunction "1_1") (pintype "passive"))
      (node (ref "R89") (pin "1") (pinfunction "1_1") (pintype "passive"))
      (node (ref "R90") (pin "1") (pinfunction "1_1") (pintype "passive"))
      (node (ref "R91") (pin "1") (pinfunction "1_1") (pintype "passive"))
      (node (ref "R97") (pin "1") (pinfunction "1_1") (pintype "passive"))
      (node (ref "R98") (pin "1") (pinfunction "1_1") (pintype "passive"))
      (node (ref "R99") (pin "1") (pinfunction "1_1") (pintype "passive"))
      (node (ref "U1") (pin "10") (pinfunction "VSS_10") (pintype "power_in"))
      (node (ref "U1") (pin "26") (pinfunction "VSS_26") (pintype "power_in"))
      (node (ref "U1") (pin "49") (pinfunction "VSS_49") (pintype "power_in"))
      (node (ref "U1") (pin "74") (pinfunction "VSS_74") (pintype "power_in"))
      (node (ref "U1") (pin "94") (pinfunction "BOOT0_94") (pintype "input"))
      (node (ref "U1") (pin "99") (pinfunction "VSS_99") (pintype "power_in"))
      (node (ref "U2") (pin "4") (pinfunction "GND_4") (pintype "passive"))
    )
    (net (code "75") (name "Net-(C30-Pad1)") (class "Default")
      (node (ref "C30") (pin "1") (pinfunction "1_1") (pintype "passive"))
      (node (ref "R87") (pin "2") (pinfunction "2_2") (pintype "passive"))
    )
    (net (code "76") (name "Net-(C31-Pad1)") (class "Default")
      (node (ref "C31") (pin "1") (pinfunction "1_1") (pintype "passive"))
      (node (ref "R88") (pin "2") (pinfunction "2_2") (pintype "passive"))
    )
    (net (code "77") (name "Net-(C36-Pad1)") (class "Default")
      (node (ref "C36") (pin "1") (pinfunction "1_1") (pintype "passive"))
      (node (ref "R99") (pin "2") (pinfunction "2_2") (pintype "passive"))
    )
    (net (code "78") (name "Net-(C37-Pad1)") (class "Default")
      (node (ref "C37") (pin "1") (pinfunction "1_1") (pintype "passive"))
      (node (ref "R100") (pin "2") (pinfunction "2_2") (pintype "passive"))
    )
    (net (code "79") (name "Net-(D28-OUT)") (class "Default")
      (node (ref "C11") (pin "2") (pinfunction "2_2") (pintype "passive"))
      (node (ref "D28") (pin "2") (pinfunction "OUT_2") (pintype "passive"))
      (node (ref "R78") (pin "1") (pinfunction "1_1") (pintype "passive"))
    )
    (net (code "80") (name "Net-(D31-PROG)") (class "Default")
      (node (ref "D31") (pin "2") (pinfunction "PROG_2") (pintype "passive"))
      (node (ref "R91") (pin "2") (pinfunction "2_2") (pintype "passive"))
    )
    (net (code "81") (name "Net-(P4-Pad2)") (class "Default")
      (node (ref "P4") (pin "2") (pinfunction "2_2") (pintype "passive"))
      (node (ref "R113") (pin "3") (pinfunction "3_3") (pintype "passive"))
    )
    (net (code "82") (name "Net-(P4-Pad4)") (class "Default")
      (node (ref "P4") (pin "4") (pinfunction "4_4") (pintype "passive"))
      (node (ref "R113") (pin "2") (pinfunction "2_2") (pintype "passive"))
    )
    (net (code "83") (name "Net-(P4-Pad5)") (class "Default")
      (node (ref "P4") (pin "5") (pinfunction "5_5") (pintype "passive"))
      (node (ref "R113") (pin "1") (pinfunction "1_1") (pintype "passive"))
    )
    (net (code "84") (name "Net-(Q51-G)") (class "Default")
      (node (ref "C19") (pin "2") (pinfunction "2_2") (pintype "passive"))
      (node (ref "Q51") (pin "1") (pinfunction "G_1") (pintype "passive"))
      (node (ref "R80") (pin "2") (pinfunction "2_2") (pintype "passive"))
    )
    (net (code "85") (name "Net-(Q52-G)") (class "Default")
      (node (ref "C28") (pin "2") (pinfunction "2_2") (pintype "passive"))
      (node (ref "Q52") (pin "1") (pinfunction "G_1") (pintype "passive"))
      (node (ref "R84") (pin "2") (pinfunction "2_2") (pintype "passive"))
    )
    (net (code "86") (name "Net-(Q53-D)") (class "Default")
      (node (ref "C30") (pin "2") (pinfunction "2_2") (pintype "passive"))
      (node (ref "L1") (pin "1") (pinfunction "1_1") (pintype "passive"))
      (node (ref "Q53") (pin "3") (pinfunction "D_3") (pintype "passive"))
      (node (ref "Q54") (pin "3") (pinfunction "D_3") (pintype "passive"))
    )
    (net (code "87") (name "Net-(Q55-D)") (class "Default")
      (node (ref "C36") (pin "2") (pinfunction "2_2") (pintype "passive"))
      (node (ref "L2") (pin "1") (pinfunction "1_1") (pintype "passive"))
      (node (ref "Q55") (pin "3") (pinfunction "D_3") (pintype "passive"))
      (node (ref "Q56") (pin "3") (pinfunction "D_3") (pintype "passive"))
    )
    (net (code "88") (name "Net-(U1A-PH0-OSC_IN(PH0))") (class "Default")
      (node (ref "C23") (pin "1") (pinfunction "1_1") (pintype "passive"))
      (node (ref "U1") (pin "12") (pinfunction "PH0-OSC_IN(PH0)_12") (pintype "bidirectional"))
      (node (ref "Y1") (pin "2") (pinfunction "OSC2_2") (pintype "passive"))
    )
    (net (code "89") (name "Net-(U1A-PH1-OSC_OUT(PH1))") (class "Default")
      (node (ref "C24") (pin "1") (pinfunction "1_1") (pintype "passive"))
      (node (ref "U1") (pin "13") (pinfunction "PH1-OSC_OUT(PH1)_13") (pintype "bidirectional"))
      (node (ref "Y1") (pin "1") (pinfunction "OSC1_1") (pintype "passive"))
    )
    (net (code "90") (name "Net-(U1A-VCAP_1)") (class "Default")
      (node (ref "C21") (pin "2") (pinfunction "2_2") (pintype "passive"))
      (node (ref "U1") (pin "48") (pinfunction "VCAP_1_48") (pintype "power_in"))
    )
    (net (code "91") (name "Net-(U1A-VCAP_2)") (class "Default")
      (node (ref "C22") (pin "2") (pinfunction "2_2") (pintype "passive"))
      (node (ref "U1") (pin "73") (pinfunction "VCAP_2_73") (pintype "power_in"))
    )
    (net (code "92") (name "Net-(U1B-VREF+)") (class "Default")
      (node (ref "C16") (pin "2") (pinfunction "2_2") (pintype "passive"))
      (node (ref "R79") (pin "1") (pinfunction "1_1") (pintype "passive"))
      (node (ref "U1") (pin "20") (pinfunction "VREF+_20") (pintype "power_in"))
    )
    (net (code "93") (name "VBAT") (class "Default")
      (node (ref "C39") (pin "2") (pinfunction "2_2") (pintype "passive"))
      (node (ref "P2") (pin "2") (pinfunction "2_2") (pintype "passive"))
      (node (ref "S1") (pin "2") (pinfunction "2_2") (pintype "passive"))
    )
    (net (code "94") (name "VCCA") (class "Default")
      (node (ref "C1") (pin "1") (pinfunction "1_1") (pintype "passive"))
      (node (ref "C12") (pin "2") (pinfunction "2_2") (pintype "passive"))
      (node (ref "C4") (pin "1") (pinfunction "1_1") (pintype "passive"))
      (node (ref "R78") (pin "2") (pinfunction "2_2") (pintype "passive"))
      (node (ref "R79") (pin "2") (pinfunction "2_2") (pintype "passive"))
      (node (ref "U1") (pin "21") (pinfunction "VDDA_21") (pintype "power_in"))
    )
    (net (code "95") (name "VDD") (class "Default")
      (node (ref "C10") (pin "2") (pinfunction "2_2") (pintype "passive"))
      (node (ref "C13") (pin "2") (pinfunction "2_2") (pintype "passive"))
      (node (ref "C18") (pin "2") (pinfunction "2_2") (pintype "passive"))
      (node (ref "C19") (pin "1") (pinfunction "1_1") (pintype "passive"))
      (node (ref "C27") (pin "2") (pinfunction "2_2") (pintype "passive"))
      (node (ref "C28") (pin "1") (pinfunction "1_1") (pintype "passive"))
      (node (ref "D27") (pin "3") (pinfunction "INPUT_3") (pintype "passive"))
      (node (ref "D28") (pin "3") (pinfunction "INPUT_3") (pintype "passive"))
      (node (ref "D29") (pin "3") (pinfunction "INPUT_3") (pintype "passive"))
      (node (ref "D30") (pin "3") (pinfunction "INPUT_3") (pintype "passive"))
      (node (ref "Q51") (pin "2") (pinfunction "S_2") (pintype "passive"))
      (node (ref "Q52") (pin "2") (pinfunction "S_2") (pintype "passive"))
    )
    (net (code "96") (name "VIN") (class "Default")
      (node (ref "C26") (pin "2") (pinfunction "2_2") (pintype "passive"))
      (node (ref "Q52") (pin "3") (pinfunction "D_3") (pintype "passive"))
      (node (ref "R114") (pin "2") (pinfunction "2_2") (pintype "passive"))
      (node (ref "S1") (pin "1") (pinfunction "1_1") (pintype "passive"))
    )
    (net (code "97") (name "VMCU") (class "Default")
      (node (ref "C15") (pin "2") (pinfunction "2_2") (pintype "passive"))
      (node (ref "C25") (pin "2") (pinfunction "2_2") (pintype "passive"))
      (node (ref "C3") (pin "2") (pinfunction "2_2") (pintype "passive"))
      (node (ref "C5") (pin "2") (pinfunction "2_2") (pintype "passive"))
      (node (ref "C6") (pin "2") (pinfunction "2_2") (pintype "passive"))
      (node (ref "C7") (pin "2") (pinfunction "2_2") (pintype "passive"))
      (node (ref "C8") (pin "2") (pinfunction "2_2") (pintype "passive"))
      (node (ref "C9") (pin "2") (pinfunction "2_2") (pintype "passive"))
      (node (ref "D27") (pin "2") (pinfunction "OUT_2") (pintype "passive"))
      (node (ref "D30") (pin "2") (pinfunction "OUT_2") (pintype "passive"))
      (node (ref "P4") (pin "1") (pinfunction "1_1") (pintype "passive"))
      (node (ref "R82") (pin "1") (pinfunction "1_1") (pintype "passive"))
      (node (ref "R83") (pin "1") (pinfunction "1_1") (pintype "passive"))
      (node (ref "R95") (pin "2") (pinfunction "2_2") (pintype "passive"))
      (node (ref "R96") (pin "2") (pinfunction "2_2") (pintype "passive"))
      (node (ref "U1") (pin "100") (pinfunction "VDD_100") (pintype "power_in"))
      (node (ref "U1") (pin "11") (pinfunction "VDD_11") (pintype "power_in"))
      (node (ref "U1") (pin "27") (pinfunction "VDD_27") (pintype "power_in"))
      (node (ref "U1") (pin "50") (pinfunction "VDD_50") (pintype "power_in"))
      (node (ref "U1") (pin "6") (pinfunction "VBAT_6") (pintype "power_in"))
      (node (ref "U1") (pin "75") (pinfunction "VDD_75") (pintype "power_in"))
      (node (ref "U2") (pin "7") (pinfunction "~{HOLD}_7") (pintype "passive"))
      (node (ref "U2") (pin "8") (pinfunction "VDD_8") (pintype "passive"))
    )
    (net (code "98") (name "VSPK") (class "Default")
      (node (ref "C14") (pin "2") (pinfunction "2_2") (pintype "passive"))
      (node (ref "C32") (pin "2") (pinfunction "2_2") (pintype "passive"))
      (node (ref "C38") (pin "2") (pinfunction "2_2") (pintype "passive"))
      (node (ref "D29") (pin "2") (pinfunction "OUT_2") (pintype "passive"))
      (node (ref "Q54") (pin "2") (pinfunction "S_2") (pintype "passive"))
      (node (ref "Q56") (pin "2") (pinfunction "S_2") (pintype "passive"))
      (node (ref "R103") (pin "2") (pinfunction "2_2") (pintype "passive"))
      (node (ref "R105") (pin "2") (pinfunction "2_2") (pintype "passive"))
      (node (ref "R106") (pin "2") (pinfunction "2_2") (pintype "passive"))
      (node (ref "R92") (pin "2") (pinfunction "2_2") (pintype "passive"))
      (node (ref "R93") (pin "2") (pinfunction "2_2") (pintype "passive"))
      (node (ref "R94") (pin "2") (pinfunction "2_2") (pintype "passive"))
    )
    (net (code "99") (name "VUSB") (class "Default")
      (node (ref "C17") (pin "2") (pinfunction "2_2") (pintype "passive"))
      (node (ref "C33") (pin "2") (pinfunction "2_2") (pintype "passive"))
      (node (ref "D31") (pin "4") (pinfunction "VCC_4") (pintype "passive"))
      (node (ref "P3") (pin "5") (pinfunction "VDD_5") (pintype "passive"))
      (node (ref "Q51") (pin "3") (pinfunction "D_3") (pintype "passive"))
      (node (ref "R104") (pin "2") (pinfunction "2_2") (pintype "passive"))
    )
    (net (code "100") (name "unconnected-(P3-DM-Pad4)") (class "Default")
      (node (ref "P3") (pin "4") (pinfunction "DM_4") (pintype "passive"))
    )
    (net (code "101") (name "unconnected-(P3-DP-Pad3)") (class "Default")
      (node (ref "P3") (pin "3") (pinfunction "DP_3") (pintype "passive"))
    )
    (net (code "102") (name "unconnected-(P3-ID-Pad2)") (class "Default")
      (node (ref "P3") (pin "2") (pinfunction "ID_2") (pintype "passive"))
    )
    (net (code "103") (name "unconnected-(P4-Pad6)") (class "Default")
      (node (ref "P4") (pin "6") (pinfunction "6_6") (pintype "passive"))
    )
    (net (code "104") (name "unconnected-(U1A-PA0-WKUP(PA0)-Pad22)") (class "Default")
      (node (ref "U1") (pin "22") (pinfunction "PA0-WKUP(PA0)_22") (pintype "bidirectional"))
    )
    (net (code "105") (name "unconnected-(U1A-PA1-Pad23)") (class "Default")
      (node (ref "U1") (pin "23") (pinfunction "PA1_23") (pintype "bidirectional"))
    )
    (net (code "106") (name "unconnected-(U1A-PA2-Pad24)") (class "Default")
      (node (ref "U1") (pin "24") (pinfunction "PA2_24") (pintype "bidirectional"))
    )
    (net (code "107") (name "unconnected-(U1A-PA6-Pad30)") (class "Default")
      (node (ref "U1") (pin "30") (pinfunction "PA6_30") (pintype "bidirectional"))
    )
    (net (code "108") (name "unconnected-(U1A-PA11-Pad70)") (class "Default")
      (node (ref "U1") (pin "70") (pinfunction "PA11_70") (pintype "bidirectional"))
    )
    (net (code "109") (name "unconnected-(U1A-PA12-Pad71)") (class "Default")
      (node (ref "U1") (pin "71") (pinfunction "PA12_71") (pintype "bidirectional"))
    )
    (net (code "110") (name "unconnected-(U1A-PA15(JTDI)-Pad77)") (class "Default")
      (node (ref "U1") (pin "77") (pinfunction "PA15(JTDI)_77") (pintype "bidirectional"))
    )
    (net (code "111") (name "unconnected-(U1A-PD11-Pad58)") (class "Default")
      (node (ref "U1") (pin "58") (pinfunction "PD11_58") (pintype "bidirectional"))
    )
    (net (code "112") (name "unconnected-(U1A-PD12-Pad59)") (class "Default")
      (node (ref "U1") (pin "59") (pinfunction "PD12_59") (pintype "bidirectional"))
    )
    (net (code "113") (name "unconnected-(U1A-PD13-Pad60)") (class "Default")
      (node (ref "U1") (pin "60") (pinfunction "PD13_60") (pintype "bidirectional"))
    )
    (net (code "114") (name "unconnected-(U1A-PD14-Pad61)") (class "Default")
      (node (ref "U1") (pin "61") (pinfunction "PD14_61") (pintype "bidirectional"))
    )
    (net (code "115") (name "unconnected-(U1A-PD15-Pad62)") (class "Default")
      (node (ref "U1") (pin "62") (pinfunction "PD15_62") (pintype "bidirectional"))
    )
  )
)
